# Power.net
KiCad netlist of a schematic drawn in Altium Designer
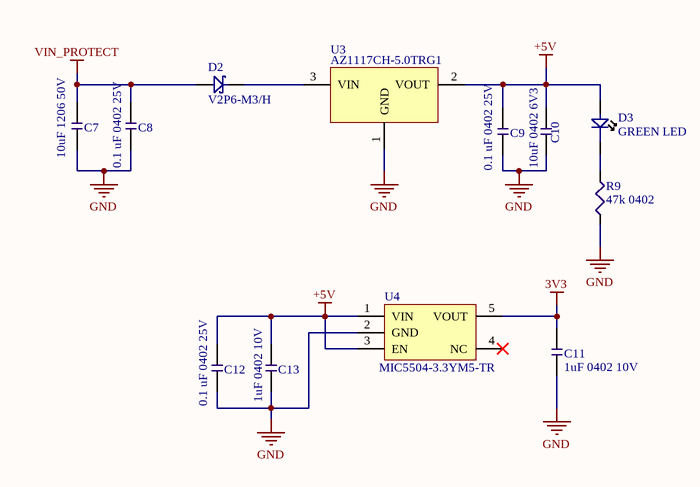
[diagram p0: Power.SchDoc]

(export (version "E")
  (design (tool "Eeschema 10.0.6"))
  (components
    (comp (ref "C7")
      (value "10uF 1206 50V")
      (footprint "CAP_1206")
      (description "10uF 1206 50V X5R 20%")
      (fields (field (name "TOLERANCE") "+/- 20%") (field (name "VOLTAGE") "50 V"))
      (libsource (lib "ON Development Vault") (part "Capacitor"))
    )
    (comp (ref "C8")
      (value "0.1 uF 0402 25V")
      (footprint "CAP_0402")
      (description "0.1UF 25V 10% X5R 0402")
      (fields (field (name "TOLERANCE") "10%") (field (name "VOLTAGE") "25V"))
      (libsource (lib "ON Development Vault") (part "Capacitor"))
    )
    (comp (ref "C9")
      (value "0.1 uF 0402 25V")
      (footprint "CAP_0402")
      (description "0.1UF 25V 10% X5R 0402")
      (fields (field (name "TOLERANCE") "10%") (field (name "VOLTAGE") "25V"))
      (libsource (lib "ON Development Vault") (part "Capacitor"))
    )
    (comp (ref "C10")
      (value "10uF 0402 6V3")
      (footprint "CAP_0402")
      (description "10uF 20% 0402 6V3 X6S")
      (fields (field (name "TOLERANCE") "20%") (field (name "VOLTAGE") "6V3"))
      (libsource (lib "ON Development Vault") (part "Capacitor"))
    )
    (comp (ref "C11")
      (value "1uF 0402 10V")
      (footprint "CAP_0402")
      (description "1uF 0402 10V 10% X5R")
      (fields (field (name "TOLERANCE") "10 %") (field (name "VOLTAGE") "10 V"))
      (libsource (lib "ON Development Vault") (part "Capacitor"))
    )
    (comp (ref "C12")
      (value "0.1 uF 0402 25V")
      (footprint "CAP_0402")
      (description "0.1UF 25V 10% X5R 0402")
      (fields (field (name "TOLERANCE") "10%") (field (name "VOLTAGE") "25V"))
      (libsource (lib "ON Development Vault") (part "Capacitor"))
    )
    (comp (ref "C13")
      (value "1uF 0402 10V")
      (footprint "CAP_0402")
      (description "1uF 0402 10V 10% X5R")
      (fields (field (name "TOLERANCE") "10 %") (field (name "VOLTAGE") "10 V"))
      (libsource (lib "ON Development Vault") (part "Capacitor"))
    )
    (comp (ref "D2")
      (value "V2P6-M3/H")
      (footprint "MicroSMP")
      (description "DIODE SCHOTTKY 60V 2A MICROSMP")
      (libsource (lib "ON Development Vault") (part "Schottky"))
    )
    (comp (ref "D3")
      (value "GREEN LED")
      (footprint "0402 LED")
      (description "0402 SMD LED")
      (fields (field (name "MFG. PART NUMBER") "LTST-C281KGKT"))
      (libsource (lib "ON Development Vault") (part "LED"))
    )
    (comp (ref "R9")
      (value "47k 0402")
      (footprint "RES_0402")
      (description "RES SMD 47K OHM 1% 1/16W 0402")
      (fields (field (name "POWER") "1/16W") (field (name "TOLERANCE") "1%"))
      (libsource (lib "ON Development Vault") (part "Resistor"))
    )
    (comp (ref "U3")
      (value "AZ1117CH-5.0TRG1")
      (footprint "SOT230P700X180-4N")
      (description "IC REG LINEAR 5V 800MA SOT223")
      (libsource (lib "ON Development Vault") (part "AZ1117CH"))
    )
    (comp (ref "U4")
      (value "MIC5504-3.3YM5-TR")
      (footprint "SOT95P280X130-5N")
      (description "LDO Voltage Regulators Single 300mA")
      (libsource (lib "ON Development Vault") (part "MIC5504"))
    )
  )
  (nets
    (net (code "1") (name "+5V") (class "Default")
      (node (ref "C10") (pin "2") (pinfunction "2_2") (pintype "passive"))
      (node (ref "C12") (pin "2") (pinfunction "2_2") (pintype "passive"))
      (node (ref "C13") (pin "2") (pinfunction "2_2") (pintype "passive"))
      (node (ref "C9") (pin "2") (pinfunction "2_2") (pintype "passive"))
      (node (ref "D3") (pin "1") (pinfunction "1_1") (pintype "passive"))
      (node (ref "U3") (pin "2") (pinfunction "VOUT_2") (pintype "passive"))
      (node (ref "U4") (pin "1") (pinfunction "VIN_1") (pintype "passive"))
      (node (ref "U4") (pin "3") (pinfunction "EN_3") (pintype "passive"))
    )
    (net (code "2") (name "3V3") (class "Default")
      (node (ref "C11") (pin "2") (pinfunction "2_2") (pintype "passive"))
      (node (ref "U4") (pin "5") (pinfunction "VOUT_5") (pintype "passive"))
    )
    (net (code "3") (name "GND") (class "Default")
      (node (ref "C10") (pin "1") (pinfunction "1_1") (pintype "passive"))
      (node (ref "C11") (pin "1") (pinfunction "1_1") (pintype "passive"))
      (node (ref "C12") (pin "1") (pinfunction "1_1") (pintype "passive"))
      (node (ref "C13") (pin "1") (pinfunction "1_1") (pintype "passive"))
      (node (ref "C7") (pin "1") (pinfunction "1_1") (pintype "passive"))
      (node (ref "C8") (pin "1") (pinfunction "1_1") (pintype "passive"))
      (node (ref "C9") (pin "1") (pinfunction "1_1") (pintype "passive"))
      (node (ref "R9") (pin "1") (pinfunction "1_1") (pintype "passive"))
      (node (ref "U3") (pin "1") (pinfunction "GND_1") (pintype "passive"))
      (node (ref "U4") (pin "2") (pinfunction "GND_2") (pintype "passive"))
    )
    (net (code "4") (name "Net-(D3-Pad2)") (class "Default")
      (node (ref "D3") (pin "2") (pinfunction "2_2") (pintype "passive"))
      (node (ref "R9") (pin "2") (pinfunction "2_2") (pintype "passive"))
    )
    (net (code "5") (name "Net-(U3-VIN)") (class "Default")
      (node (ref "D2") (pin "2") (pinfunction "2_2") (pintype "passive"))
      (node (ref "U3") (pin "3") (pinfunction "VIN_3") (pintype "passive"))
    )
    (net (code "6") (name "VIN_PROTECT") (class "Default")
      (node (ref "C7") (pin "2") (pinfunction "2_2") (pintype "passive"))
      (node (ref "C8") (pin "2") (pinfunction "2_2") (pintype "passive"))
      (node (ref "D2") (pin "1") (pinfunction "1_1") (pintype "passive"))
    )
    (net (code "7") (name "unconnected-(U4-NC-Pad4)") (class "Default")
      (node (ref "U4") (pin "4") (pinfunction "NC_4") (pintype "passive+no_connect"))
    )
  )
)
